# daughter-double.net
KiCad netlist of a schematic drawn in EAGLE
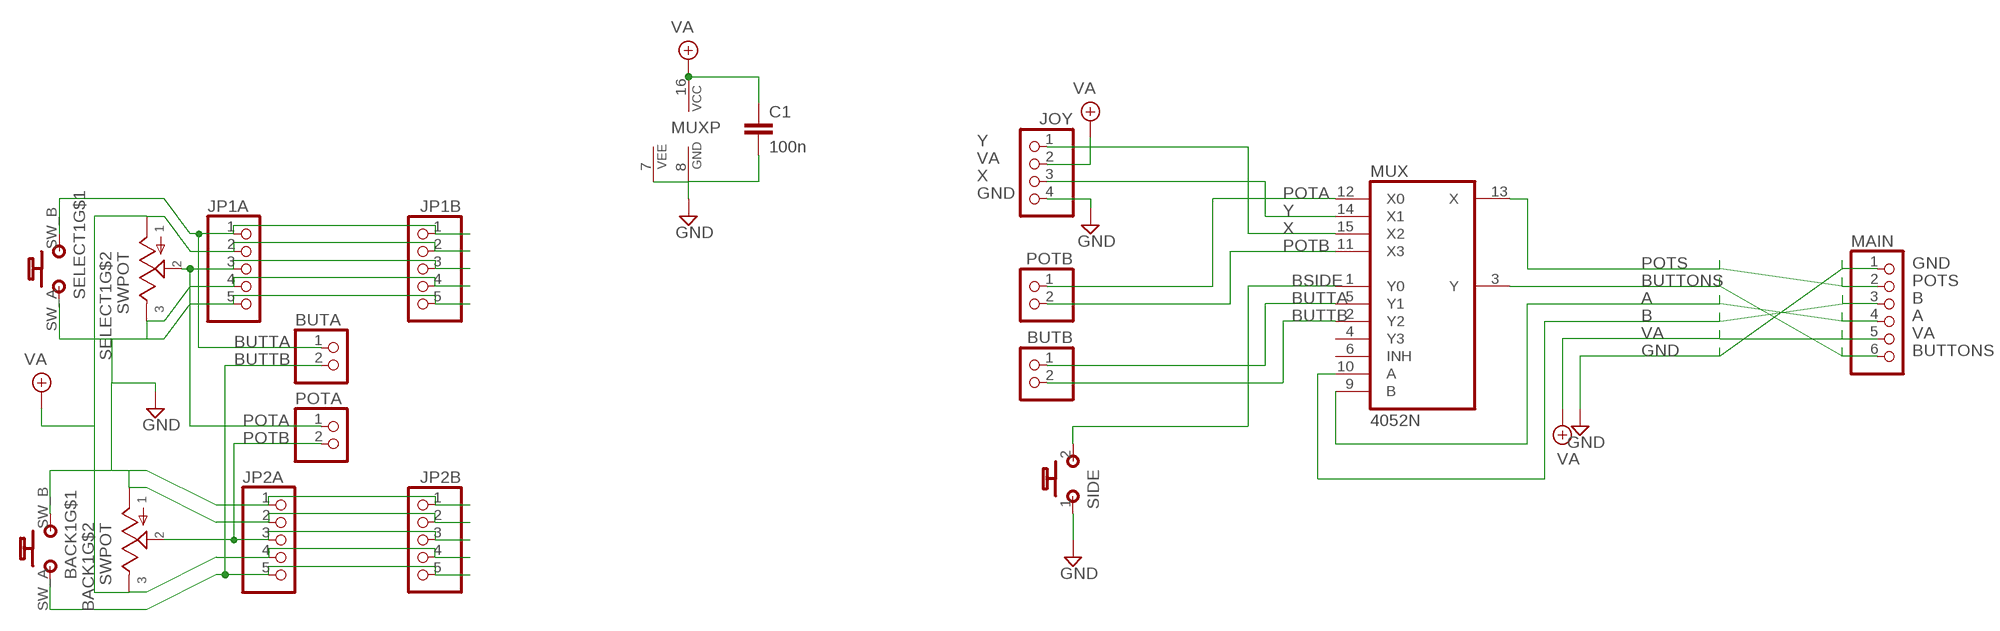
[diagram p0: schematic, sheet 1]

(export (version "E")
  (design (tool "Eeschema 10.0.6"))
  (components
    (comp (ref "BACK1")
      (value "SWPOT")
      (footprint "eagle-import:SWPOT")
      (libsource (lib "eagle-import") (part "SWPOT"))
    )
    (comp (ref "BUTA")
      (value "PINHD-1X2")
      (footprint "eagle-import:1X02")
      (libsource (lib "eagle-import") (part "PINHD-1X2"))
    )
    (comp (ref "BUTB")
      (value "PINHD-1X2")
      (footprint "eagle-import:1X02")
      (libsource (lib "eagle-import") (part "PINHD-1X2"))
    )
    (comp (ref "C1")
      (value "100n")
      (footprint "eagle-import:050X030_050_3")
      (libsource (lib "eagle-import") (part "050X030_050"))
    )
    (comp (ref "JOY")
      (value "PINHD-1X4")
      (footprint "eagle-import:1X04")
      (libsource (lib "eagle-import") (part "PINHD-1X4"))
    )
    (comp (ref "JP1A")
      (value "PINHD-1X5")
      (footprint "eagle-import:1X05")
      (libsource (lib "eagle-import") (part "PINHD-1X5"))
    )
    (comp (ref "JP1B")
      (value "PINHD-1X5")
      (footprint "eagle-import:1X05")
      (libsource (lib "eagle-import") (part "PINHD-1X5"))
    )
    (comp (ref "JP2A")
      (value "PINHD-1X5")
      (footprint "eagle-import:1X05")
      (libsource (lib "eagle-import") (part "PINHD-1X5"))
    )
    (comp (ref "JP2B")
      (value "PINHD-1X5")
      (footprint "eagle-import:1X05")
      (libsource (lib "eagle-import") (part "PINHD-1X5"))
    )
    (comp (ref "MAIN")
      (value "PINHD-1X6")
      (footprint "eagle-import:1X06")
      (libsource (lib "eagle-import") (part "PINHD-1X6"))
    )
    (comp (ref "MUX")
      (value "4052N")
      (footprint "eagle-import:DIL16")
      (libsource (lib "eagle-import") (part "4052N"))
    )
    (comp (ref "POTA")
      (value "PINHD-1X2")
      (footprint "eagle-import:1X02")
      (libsource (lib "eagle-import") (part "PINHD-1X2"))
    )
    (comp (ref "POTB")
      (value "PINHD-1X2")
      (footprint "eagle-import:1X02")
      (libsource (lib "eagle-import") (part "PINHD-1X2"))
    )
    (comp (ref "SELECT1")
      (value "SWPOT")
      (footprint "eagle-import:SWPOT")
      (libsource (lib "eagle-import") (part "SWPOT"))
    )
    (comp (ref "SIDE")
      (value "MOMENTARY")
      (footprint "eagle-import:SPST2")
      (libsource (lib "eagle-import") (part "MOMENTARY"))
    )
  )
  (nets
    (net (code "1") (name "/A") (class "Default")
      (node (ref "MAIN") (pin "4") (pinfunction "4_4") (pintype "passive"))
      (node (ref "MUX") (pin "9") (pinfunction "B_9") (pintype "input"))
    )
    (net (code "2") (name "/B") (class "Default")
      (node (ref "MAIN") (pin "3") (pinfunction "3_3") (pintype "passive"))
      (node (ref "MUX") (pin "10") (pinfunction "A_10") (pintype "input"))
    )
    (net (code "3") (name "/BSIDE") (class "Default")
      (node (ref "MUX") (pin "1") (pinfunction "Y0_1") (pintype "bidirectional"))
      (node (ref "SIDE") (pin "2") (pinfunction "S_2") (pintype "passive"))
    )
    (net (code "4") (name "/BUTTA") (class "Default")
      (node (ref "BUTA") (pin "1") (pinfunction "1_1") (pintype "passive"))
      (node (ref "BUTB") (pin "1") (pinfunction "1_1") (pintype "passive"))
      (node (ref "JP1A") (pin "1") (pinfunction "1_1") (pintype "passive"))
      (node (ref "JP1B") (pin "1") (pinfunction "1_1") (pintype "passive"))
      (node (ref "MUX") (pin "5") (pinfunction "Y1_5") (pintype "bidirectional"))
      (node (ref "SELECT1") (pin "SW_B") (pinfunction "B_B_SW_B") (pintype "passive"))
    )
    (net (code "5") (name "/BUTTB") (class "Default")
      (node (ref "BACK1") (pin "SW_A") (pinfunction "B_A_SW_A") (pintype "passive"))
      (node (ref "BUTA") (pin "2") (pinfunction "2_2") (pintype "passive"))
      (node (ref "BUTB") (pin "2") (pinfunction "2_2") (pintype "passive"))
      (node (ref "JP2A") (pin "5") (pinfunction "5_5") (pintype "passive"))
      (node (ref "JP2B") (pin "5") (pinfunction "5_5") (pintype "passive"))
      (node (ref "MUX") (pin "2") (pinfunction "Y2_2") (pintype "bidirectional"))
    )
    (net (code "6") (name "/BUTTONS") (class "Default")
      (node (ref "MAIN") (pin "6") (pinfunction "6_6") (pintype "passive"))
      (node (ref "MUX") (pin "3") (pinfunction "Y_3") (pintype "bidirectional"))
    )
    (net (code "7") (name "/POTA") (class "Default")
      (node (ref "JP1A") (pin "3") (pinfunction "3_3") (pintype "passive"))
      (node (ref "JP1B") (pin "3") (pinfunction "3_3") (pintype "passive"))
      (node (ref "MUX") (pin "12") (pinfunction "X0_12") (pintype "bidirectional"))
      (node (ref "POTA") (pin "1") (pinfunction "1_1") (pintype "passive"))
      (node (ref "POTB") (pin "1") (pinfunction "1_1") (pintype "passive"))
      (node (ref "SELECT1") (pin "POT_W") (pinfunction "POT_W_POT_W") (pintype "passive"))
    )
    (net (code "8") (name "/POTB") (class "Default")
      (node (ref "BACK1") (pin "POT_W") (pinfunction "POT_W_POT_W") (pintype "passive"))
      (node (ref "JP2A") (pin "3") (pinfunction "3_3") (pintype "passive"))
      (node (ref "JP2B") (pin "3") (pinfunction "3_3") (pintype "passive"))
      (node (ref "MUX") (pin "11") (pinfunction "X3_11") (pintype "bidirectional"))
      (node (ref "POTA") (pin "2") (pinfunction "2_2") (pintype "passive"))
      (node (ref "POTB") (pin "2") (pinfunction "2_2") (pintype "passive"))
    )
    (net (code "9") (name "/POTS") (class "Default")
      (node (ref "MAIN") (pin "2") (pinfunction "2_2") (pintype "passive"))
      (node (ref "MUX") (pin "13") (pinfunction "X_13") (pintype "bidirectional"))
    )
    (net (code "10") (name "/X") (class "Default")
      (node (ref "JOY") (pin "1") (pinfunction "1_1") (pintype "passive"))
      (node (ref "MUX") (pin "15") (pinfunction "X2_15") (pintype "bidirectional"))
    )
    (net (code "11") (name "/Y") (class "Default")
      (node (ref "JOY") (pin "3") (pinfunction "3_3") (pintype "passive"))
      (node (ref "MUX") (pin "14") (pinfunction "X1_14") (pintype "bidirectional"))
    )
    (net (code "12") (name "GND") (class "Default")
      (node (ref "BACK1") (pin "POT_B") (pinfunction "POT_B_POT_B") (pintype "passive"))
      (node (ref "BACK1") (pin "SW_B") (pinfunction "B_B_SW_B") (pintype "passive"))
      (node (ref "C1") (pin "2") (pinfunction "2_2") (pintype "passive"))
      (node (ref "JOY") (pin "4") (pinfunction "4_4") (pintype "passive"))
      (node (ref "JP1A") (pin "4") (pinfunction "4_4") (pintype "passive"))
      (node (ref "JP1A") (pin "5") (pinfunction "5_5") (pintype "passive"))
      (node (ref "JP1B") (pin "4") (pinfunction "4_4") (pintype "passive"))
      (node (ref "JP1B") (pin "5") (pinfunction "5_5") (pintype "passive"))
      (node (ref "JP2A") (pin "1") (pinfunction "1_1") (pintype "passive"))
      (node (ref "JP2A") (pin "2") (pinfunction "2_2") (pintype "passive"))
      (node (ref "JP2B") (pin "1") (pinfunction "1_1") (pintype "passive"))
      (node (ref "JP2B") (pin "2") (pinfunction "2_2") (pintype "passive"))
      (node (ref "MAIN") (pin "1") (pinfunction "1_1") (pintype "passive"))
      (node (ref "MUX") (pin "7") (pinfunction "VEE_7") (pintype "power_in"))
      (node (ref "MUX") (pin "8") (pinfunction "GND_8") (pintype "power_in"))
      (node (ref "SELECT1") (pin "POT_A") (pinfunction "POT_A_POT_A") (pintype "passive"))
      (node (ref "SELECT1") (pin "SW_A") (pinfunction "B_A_SW_A") (pintype "passive"))
      (node (ref "SIDE") (pin "1") (pinfunction "P_1") (pintype "passive"))
    )
    (net (code "13") (name "VA") (class "Default")
      (node (ref "BACK1") (pin "POT_A") (pinfunction "POT_A_POT_A") (pintype "passive"))
      (node (ref "C1") (pin "1") (pinfunction "1_1") (pintype "passive"))
      (node (ref "JOY") (pin "2") (pinfunction "2_2") (pintype "passive"))
      (node (ref "JP1A") (pin "2") (pinfunction "2_2") (pintype "passive"))
      (node (ref "JP1B") (pin "2") (pinfunction "2_2") (pintype "passive"))
      (node (ref "JP2A") (pin "4") (pinfunction "4_4") (pintype "passive"))
      (node (ref "JP2B") (pin "4") (pinfunction "4_4") (pintype "passive"))
      (node (ref "MAIN") (pin "5") (pinfunction "5_5") (pintype "passive"))
      (node (ref "MUX") (pin "16") (pinfunction "VCC_16") (pintype "power_in"))
      (node (ref "SELECT1") (pin "POT_B") (pinfunction "POT_B_POT_B") (pintype "passive"))
    )
    (net (code "14") (name "unconnected-(MUXA-INH-Pad6)") (class "Default")
      (node (ref "MUX") (pin "6") (pinfunction "INH_6") (pintype "input"))
    )
    (net (code "15") (name "unconnected-(MUXA-Y3-Pad4)") (class "Default")
      (node (ref "MUX") (pin "4") (pinfunction "Y3_4") (pintype "bidirectional"))
    )
  )
)
